# mega_pinout.net
KiCad netlist of a schematic drawn in EAGLE
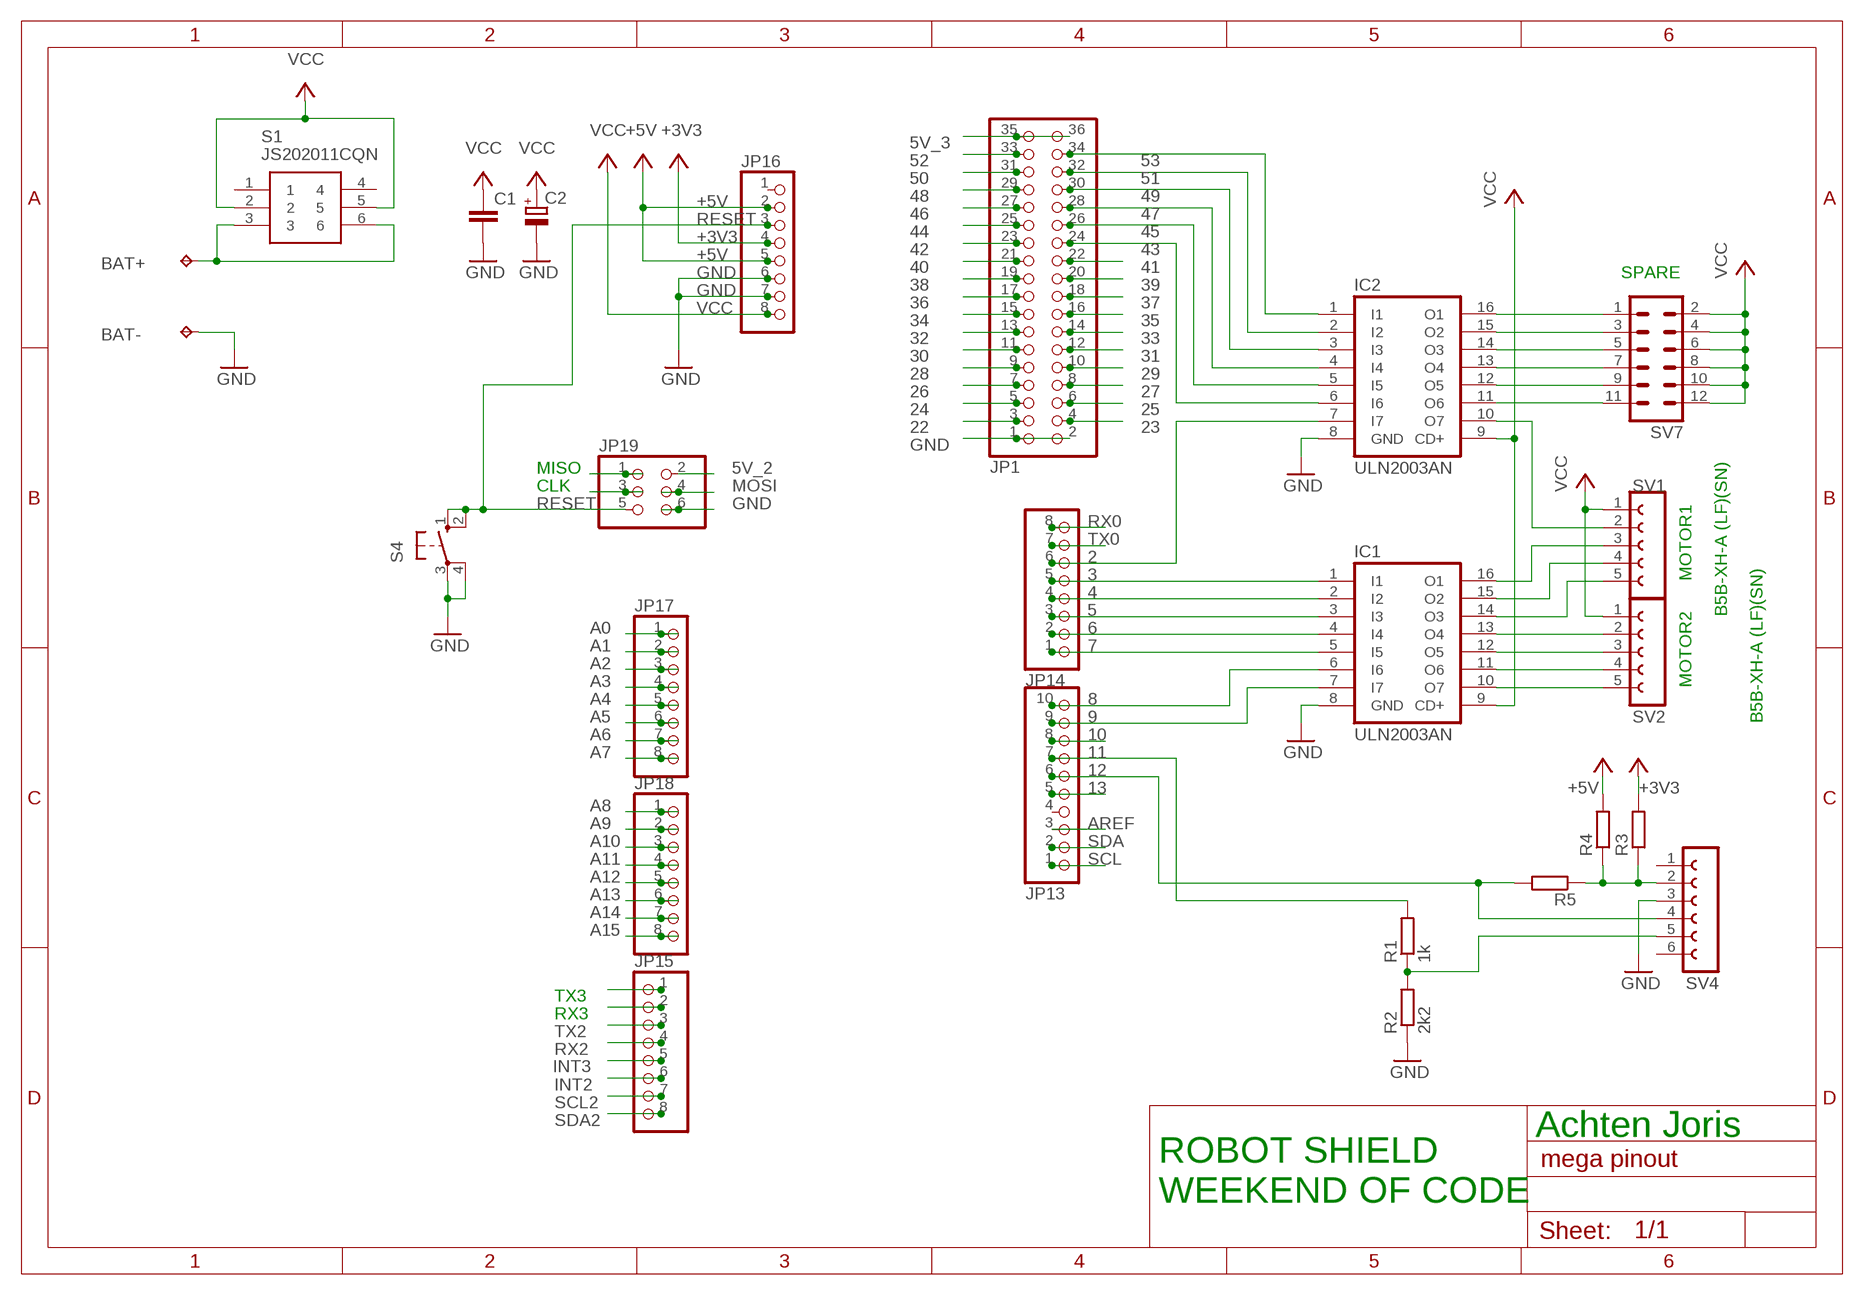
[diagram p0: schematic, sheet 1]

(export (version "E")
  (design (tool "Eeschema 10.0.6"))
  (components
    (comp (ref "BAT+")
      (value "TPPAD1-13")
      (footprint "eagle-import:P1-13")
      (libsource (lib "eagle-import") (part "TPPAD1-13"))
    )
    (comp (ref "BAT-")
      (value "TPPAD1-13")
      (footprint "eagle-import:P1-13")
      (libsource (lib "eagle-import") (part "TPPAD1-13"))
    )
    (comp (ref "C1")
      (value "C-EUC1206")
      (footprint "eagle-import:C1206")
      (libsource (lib "eagle-import") (part "C-EUC1206"))
    )
    (comp (ref "C2")
      (value "CPOL-EUE5-8.5")
      (footprint "eagle-import:E5-8,5")
      (libsource (lib "eagle-import") (part "CPOL-EUE5-8.5"))
    )
    (comp (ref "IC1")
      (value "ULN2003AN")
      (footprint "eagle-import:DIL16")
      (libsource (lib "eagle-import") (part "ULN2003AN"))
    )
    (comp (ref "IC2")
      (value "ULN2003AN")
      (footprint "eagle-import:DIL16")
      (libsource (lib "eagle-import") (part "ULN2003AN"))
    )
    (comp (ref "JP1")
      (value "PINHD-2X18")
      (footprint "eagle-import:2X18")
      (libsource (lib "eagle-import") (part "PINHD-2X18"))
    )
    (comp (ref "JP13")
      (value "PINHD-1X10")
      (footprint "eagle-import:1X10")
      (libsource (lib "eagle-import") (part "PINHD-1X10"))
    )
    (comp (ref "JP14")
      (value "PINHD-1X8")
      (footprint "eagle-import:1X08")
      (libsource (lib "eagle-import") (part "PINHD-1X8"))
    )
    (comp (ref "JP15")
      (value "PINHD-1X8")
      (footprint "eagle-import:1X08")
      (libsource (lib "eagle-import") (part "PINHD-1X8"))
    )
    (comp (ref "JP16")
      (value "PINHD-1X8")
      (footprint "eagle-import:1X08")
      (libsource (lib "eagle-import") (part "PINHD-1X8"))
    )
    (comp (ref "JP17")
      (value "PINHD-1X8")
      (footprint "eagle-import:1X08")
      (libsource (lib "eagle-import") (part "PINHD-1X8"))
    )
    (comp (ref "JP18")
      (value "PINHD-1X8")
      (footprint "eagle-import:1X08")
      (libsource (lib "eagle-import") (part "PINHD-1X8"))
    )
    (comp (ref "JP19")
      (value "PINHD-2X3")
      (footprint "eagle-import:2X03")
      (libsource (lib "eagle-import") (part "PINHD-2X3"))
    )
    (comp (ref "R1")
      (value "1k")
      (footprint "eagle-import:R0603")
      (libsource (lib "eagle-import") (part "R-EU_R0603"))
    )
    (comp (ref "R2")
      (value "2k2")
      (footprint "eagle-import:R0603")
      (libsource (lib "eagle-import") (part "R-EU_R0603"))
    )
    (comp (ref "R3")
      (value "R-EU_R0603")
      (footprint "eagle-import:R0603")
      (libsource (lib "eagle-import") (part "R-EU_R0603"))
    )
    (comp (ref "R4")
      (value "R-EU_R0603")
      (footprint "eagle-import:R0603")
      (libsource (lib "eagle-import") (part "R-EU_R0603"))
    )
    (comp (ref "R5")
      (value "R-EU_R0603")
      (footprint "eagle-import:R0603")
      (libsource (lib "eagle-import") (part "R-EU_R0603"))
    )
    (comp (ref "S1")
      (value "JS202011CQN")
      (footprint "eagle-import:JS202011CQN")
      (fields (field (name "MOUSER_PART_NUMBER") "611-JS202011CQN"))
      (libsource (lib "eagle-import") (part "JS202011CQN"))
    )
    (comp (ref "S4")
      (value "10-XX")
      (footprint "eagle-import:B3F-10XX")
      (fields (field (name "MPN") "B3F-1000"))
      (libsource (lib "eagle-import") (part "10-XX"))
    )
    (comp (ref "SV1")
      (value "FE05-1")
      (footprint "eagle-import:FE05-1")
      (libsource (lib "eagle-import") (part "FE05-1"))
    )
    (comp (ref "SV2")
      (value "FE05-1")
      (footprint "eagle-import:FE05-1")
      (libsource (lib "eagle-import") (part "FE05-1"))
    )
    (comp (ref "SV4")
      (value "FE06-1")
      (footprint "eagle-import:FE06")
      (libsource (lib "eagle-import") (part "FE06-1"))
    )
    (comp (ref "SV7")
      (value "MA06-2")
      (footprint "eagle-import:MA06-2")
      (libsource (lib "eagle-import") (part "MA06-2"))
    )
  )
  (nets
    (net (code "1") (name "+3V3") (class "Default")
      (node (ref "JP16") (pin "4") (pinfunction "4_4") (pintype "passive"))
      (node (ref "R3") (pin "2") (pinfunction "2_2") (pintype "passive"))
    )
    (net (code "2") (name "+5V") (class "Default")
      (node (ref "JP16") (pin "2") (pinfunction "2_2") (pintype "passive"))
      (node (ref "JP16") (pin "5") (pinfunction "5_5") (pintype "passive"))
      (node (ref "R4") (pin "2") (pinfunction "2_2") (pintype "passive"))
    )
    (net (code "3") (name "/2") (class "Default")
      (node (ref "IC2") (pin "7") (pinfunction "I7_7") (pintype "input"))
      (node (ref "JP14") (pin "6") (pinfunction "6_6") (pintype "passive"))
    )
    (net (code "4") (name "/3") (class "Default")
      (node (ref "IC1") (pin "1") (pinfunction "I1_1") (pintype "input"))
      (node (ref "JP14") (pin "5") (pinfunction "5_5") (pintype "passive"))
    )
    (net (code "5") (name "/4") (class "Default")
      (node (ref "IC1") (pin "2") (pinfunction "I2_2") (pintype "input"))
      (node (ref "JP14") (pin "4") (pinfunction "4_4") (pintype "passive"))
    )
    (net (code "6") (name "/5") (class "Default")
      (node (ref "IC1") (pin "3") (pinfunction "I3_3") (pintype "input"))
      (node (ref "JP14") (pin "3") (pinfunction "3_3") (pintype "passive"))
    )
    (net (code "7") (name "/5V_2") (class "Default")
      (node (ref "JP19") (pin "2") (pinfunction "2_2") (pintype "passive"))
    )
    (net (code "8") (name "/5V_3") (class "Default")
      (node (ref "JP1") (pin "35") (pinfunction "35_35") (pintype "passive"))
      (node (ref "JP1") (pin "36") (pinfunction "36_36") (pintype "passive"))
    )
    (net (code "9") (name "/6") (class "Default")
      (node (ref "IC1") (pin "4") (pinfunction "I4_4") (pintype "input"))
      (node (ref "JP14") (pin "2") (pinfunction "2_2") (pintype "passive"))
    )
    (net (code "10") (name "/7") (class "Default")
      (node (ref "IC1") (pin "5") (pinfunction "I5_5") (pintype "input"))
      (node (ref "JP14") (pin "1") (pinfunction "1_1") (pintype "passive"))
    )
    (net (code "11") (name "/8") (class "Default")
      (node (ref "IC1") (pin "6") (pinfunction "I6_6") (pintype "input"))
      (node (ref "JP13") (pin "10") (pinfunction "10_10") (pintype "passive"))
    )
    (net (code "12") (name "/9") (class "Default")
      (node (ref "IC1") (pin "7") (pinfunction "I7_7") (pintype "input"))
      (node (ref "JP13") (pin "9") (pinfunction "9_9") (pintype "passive"))
    )
    (net (code "13") (name "/10") (class "Default")
      (node (ref "JP13") (pin "8") (pinfunction "8_8") (pintype "passive"))
    )
    (net (code "14") (name "/11") (class "Default")
      (node (ref "JP13") (pin "7") (pinfunction "7_7") (pintype "passive"))
      (node (ref "R1") (pin "2") (pinfunction "2_2") (pintype "passive"))
    )
    (net (code "15") (name "/12") (class "Default")
      (node (ref "JP13") (pin "6") (pinfunction "6_6") (pintype "passive"))
      (node (ref "R5") (pin "2") (pinfunction "2_2") (pintype "passive"))
      (node (ref "SV4") (pin "4") (pinfunction "4_4") (pintype "passive"))
    )
    (net (code "16") (name "/13") (class "Default")
      (node (ref "JP13") (pin "5") (pinfunction "5_5") (pintype "passive"))
    )
    (net (code "17") (name "/22") (class "Default")
      (node (ref "JP1") (pin "3") (pinfunction "3_3") (pintype "passive"))
    )
    (net (code "18") (name "/23") (class "Default")
      (node (ref "JP1") (pin "4") (pinfunction "4_4") (pintype "passive"))
    )
    (net (code "19") (name "/24") (class "Default")
      (node (ref "JP1") (pin "5") (pinfunction "5_5") (pintype "passive"))
    )
    (net (code "20") (name "/25") (class "Default")
      (node (ref "JP1") (pin "6") (pinfunction "6_6") (pintype "passive"))
    )
    (net (code "21") (name "/26") (class "Default")
      (node (ref "JP1") (pin "7") (pinfunction "7_7") (pintype "passive"))
    )
    (net (code "22") (name "/27") (class "Default")
      (node (ref "JP1") (pin "8") (pinfunction "8_8") (pintype "passive"))
    )
    (net (code "23") (name "/28") (class "Default")
      (node (ref "JP1") (pin "9") (pinfunction "9_9") (pintype "passive"))
    )
    (net (code "24") (name "/29") (class "Default")
      (node (ref "JP1") (pin "10") (pinfunction "10_10") (pintype "passive"))
    )
    (net (code "25") (name "/30") (class "Default")
      (node (ref "JP1") (pin "11") (pinfunction "11_11") (pintype "passive"))
    )
    (net (code "26") (name "/31") (class "Default")
      (node (ref "JP1") (pin "12") (pinfunction "12_12") (pintype "passive"))
    )
    (net (code "27") (name "/32") (class "Default")
      (node (ref "JP1") (pin "13") (pinfunction "13_13") (pintype "passive"))
    )
    (net (code "28") (name "/33") (class "Default")
      (node (ref "JP1") (pin "14") (pinfunction "14_14") (pintype "passive"))
    )
    (net (code "29") (name "/34") (class "Default")
      (node (ref "JP1") (pin "15") (pinfunction "15_15") (pintype "passive"))
    )
    (net (code "30") (name "/35") (class "Default")
      (node (ref "JP1") (pin "16") (pinfunction "16_16") (pintype "passive"))
    )
    (net (code "31") (name "/36") (class "Default")
      (node (ref "JP1") (pin "17") (pinfunction "17_17") (pintype "passive"))
    )
    (net (code "32") (name "/37") (class "Default")
      (node (ref "JP1") (pin "18") (pinfunction "18_18") (pintype "passive"))
    )
    (net (code "33") (name "/38") (class "Default")
      (node (ref "JP1") (pin "19") (pinfunction "19_19") (pintype "passive"))
    )
    (net (code "34") (name "/39") (class "Default")
      (node (ref "JP1") (pin "20") (pinfunction "20_20") (pintype "passive"))
    )
    (net (code "35") (name "/40") (class "Default")
      (node (ref "JP1") (pin "21") (pinfunction "21_21") (pintype "passive"))
    )
    (net (code "36") (name "/41") (class "Default")
      (node (ref "JP1") (pin "22") (pinfunction "22_22") (pintype "passive"))
    )
    (net (code "37") (name "/42") (class "Default")
      (node (ref "JP1") (pin "23") (pinfunction "23_23") (pintype "passive"))
    )
    (net (code "38") (name "/43") (class "Default")
      (node (ref "IC2") (pin "6") (pinfunction "I6_6") (pintype "input"))
      (node (ref "JP1") (pin "24") (pinfunction "24_24") (pintype "passive"))
    )
    (net (code "39") (name "/44") (class "Default")
      (node (ref "JP1") (pin "25") (pinfunction "25_25") (pintype "passive"))
    )
    (net (code "40") (name "/45") (class "Default")
      (node (ref "IC2") (pin "5") (pinfunction "I5_5") (pintype "input"))
      (node (ref "JP1") (pin "26") (pinfunction "26_26") (pintype "passive"))
    )
    (net (code "41") (name "/46") (class "Default")
      (node (ref "JP1") (pin "27") (pinfunction "27_27") (pintype "passive"))
    )
    (net (code "42") (name "/47") (class "Default")
      (node (ref "IC2") (pin "4") (pinfunction "I4_4") (pintype "input"))
      (node (ref "JP1") (pin "28") (pinfunction "28_28") (pintype "passive"))
    )
    (net (code "43") (name "/48") (class "Default")
      (node (ref "JP1") (pin "29") (pinfunction "29_29") (pintype "passive"))
    )
    (net (code "44") (name "/49") (class "Default")
      (node (ref "IC2") (pin "3") (pinfunction "I3_3") (pintype "input"))
      (node (ref "JP1") (pin "30") (pinfunction "30_30") (pintype "passive"))
    )
    (net (code "45") (name "/50") (class "Default")
      (node (ref "JP1") (pin "31") (pinfunction "31_31") (pintype "passive"))
    )
    (net (code "46") (name "/51") (class "Default")
      (node (ref "IC2") (pin "2") (pinfunction "I2_2") (pintype "input"))
      (node (ref "JP1") (pin "32") (pinfunction "32_32") (pintype "passive"))
    )
    (net (code "47") (name "/52") (class "Default")
      (node (ref "JP1") (pin "33") (pinfunction "33_33") (pintype "passive"))
    )
    (net (code "48") (name "/53") (class "Default")
      (node (ref "IC2") (pin "1") (pinfunction "I1_1") (pintype "input"))
      (node (ref "JP1") (pin "34") (pinfunction "34_34") (pintype "passive"))
    )
    (net (code "49") (name "/A0") (class "Default")
      (node (ref "JP17") (pin "1") (pinfunction "1_1") (pintype "passive"))
    )
    (net (code "50") (name "/A1") (class "Default")
      (node (ref "JP17") (pin "2") (pinfunction "2_2") (pintype "passive"))
    )
    (net (code "51") (name "/A2") (class "Default")
      (node (ref "JP17") (pin "3") (pinfunction "3_3") (pintype "passive"))
    )
    (net (code "52") (name "/A3") (class "Default")
      (node (ref "JP17") (pin "4") (pinfunction "4_4") (pintype "passive"))
    )
    (net (code "53") (name "/A4") (class "Default")
      (node (ref "JP17") (pin "5") (pinfunction "5_5") (pintype "passive"))
    )
    (net (code "54") (name "/A5") (class "Default")
      (node (ref "JP17") (pin "6") (pinfunction "6_6") (pintype "passive"))
    )
    (net (code "55") (name "/A6") (class "Default")
      (node (ref "JP17") (pin "7") (pinfunction "7_7") (pintype "passive"))
    )
    (net (code "56") (name "/A7") (class "Default")
      (node (ref "JP17") (pin "8") (pinfunction "8_8") (pintype "passive"))
    )
    (net (code "57") (name "/A8") (class "Default")
      (node (ref "JP18") (pin "1") (pinfunction "1_1") (pintype "passive"))
    )
    (net (code "58") (name "/A9") (class "Default")
      (node (ref "JP18") (pin "2") (pinfunction "2_2") (pintype "passive"))
    )
    (net (code "59") (name "/A10") (class "Default")
      (node (ref "JP18") (pin "3") (pinfunction "3_3") (pintype "passive"))
    )
    (net (code "60") (name "/A11") (class "Default")
      (node (ref "JP18") (pin "4") (pinfunction "4_4") (pintype "passive"))
    )
    (net (code "61") (name "/A12") (class "Default")
      (node (ref "JP18") (pin "5") (pinfunction "5_5") (pintype "passive"))
    )
    (net (code "62") (name "/A13") (class "Default")
      (node (ref "JP18") (pin "6") (pinfunction "6_6") (pintype "passive"))
    )
    (net (code "63") (name "/A14") (class "Default")
      (node (ref "JP18") (pin "7") (pinfunction "7_7") (pintype "passive"))
    )
    (net (code "64") (name "/A15") (class "Default")
      (node (ref "JP18") (pin "8") (pinfunction "8_8") (pintype "passive"))
    )
    (net (code "65") (name "/AREF") (class "Default")
      (node (ref "JP13") (pin "3") (pinfunction "3_3") (pintype "passive"))
    )
    (net (code "66") (name "/CLK") (class "Default")
      (node (ref "JP19") (pin "3") (pinfunction "3_3") (pintype "passive"))
    )
    (net (code "67") (name "/INT2") (class "Default")
      (node (ref "JP15") (pin "6") (pinfunction "6_6") (pintype "passive"))
    )
    (net (code "68") (name "/INT3") (class "Default")
      (node (ref "JP15") (pin "5") (pinfunction "5_5") (pintype "passive"))
    )
    (net (code "69") (name "/MISO") (class "Default")
      (node (ref "JP19") (pin "1") (pinfunction "1_1") (pintype "passive"))
    )
    (net (code "70") (name "/MOSI") (class "Default")
      (node (ref "JP19") (pin "4") (pinfunction "4_4") (pintype "passive"))
    )
    (net (code "71") (name "/RESET") (class "Default")
      (node (ref "JP16") (pin "3") (pinfunction "3_3") (pintype "passive"))
      (node (ref "JP19") (pin "5") (pinfunction "5_5") (pintype "passive"))
      (node (ref "S4") (pin "1") (pinfunction "S_1") (pintype "passive"))
      (node (ref "S4") (pin "2") (pinfunction "S1_2") (pintype "passive"))
    )
    (net (code "72") (name "/RX0") (class "Default")
      (node (ref "JP14") (pin "8") (pinfunction "8_8") (pintype "passive"))
    )
    (net (code "73") (name "/RX2") (class "Default")
      (node (ref "JP15") (pin "4") (pinfunction "4_4") (pintype "passive"))
    )
    (net (code "74") (name "/RX3") (class "Default")
      (node (ref "JP15") (pin "2") (pinfunction "2_2") (pintype "passive"))
    )
    (net (code "75") (name "/SCL") (class "Default")
      (node (ref "JP13") (pin "1") (pinfunction "1_1") (pintype "passive"))
    )
    (net (code "76") (name "/SCL2") (class "Default")
      (node (ref "JP15") (pin "7") (pinfunction "7_7") (pintype "passive"))
    )
    (net (code "77") (name "/SDA") (class "Default")
      (node (ref "JP13") (pin "2") (pinfunction "2_2") (pintype "passive"))
    )
    (net (code "78") (name "/SDA2") (class "Default")
      (node (ref "JP15") (pin "8") (pinfunction "8_8") (pintype "passive"))
    )
    (net (code "79") (name "/TX0") (class "Default")
      (node (ref "JP14") (pin "7") (pinfunction "7_7") (pintype "passive"))
    )
    (net (code "80") (name "/TX2") (class "Default")
      (node (ref "JP15") (pin "3") (pinfunction "3_3") (pintype "passive"))
    )
    (net (code "81") (name "/TX3") (class "Default")
      (node (ref "JP15") (pin "1") (pinfunction "1_1") (pintype "passive"))
    )
    (net (code "82") (name "GND") (class "Default")
      (node (ref "BAT-") (pin "TP") (pinfunction "TP_TP") (pintype "input"))
      (node (ref "C1") (pin "2") (pinfunction "2_2") (pintype "passive"))
      (node (ref "C2") (pin "-") (pinfunction "-_-") (pintype "passive"))
      (node (ref "IC1") (pin "8") (pinfunction "GND_8") (pintype "power_in"))
      (node (ref "IC2") (pin "8") (pinfunction "GND_8") (pintype "power_in"))
      (node (ref "JP1") (pin "1") (pinfunction "1_1") (pintype "passive"))
      (node (ref "JP1") (pin "2") (pinfunction "2_2") (pintype "passive"))
      (node (ref "JP16") (pin "6") (pinfunction "6_6") (pintype "passive"))
      (node (ref "JP16") (pin "7") (pinfunction "7_7") (pintype "passive"))
      (node (ref "JP19") (pin "6") (pinfunction "6_6") (pintype "passive"))
      (node (ref "R2") (pin "1") (pinfunction "1_1") (pintype "passive"))
      (node (ref "S4") (pin "3") (pinfunction "P_3") (pintype "passive"))
      (node (ref "S4") (pin "4") (pinfunction "P1_4") (pintype "passive"))
      (node (ref "SV4") (pin "3") (pinfunction "3_3") (pintype "passive"))
    )
    (net (code "83") (name "Net-(BAT+-PadTP)") (class "Default")
      (node (ref "BAT+") (pin "TP") (pinfunction "TP_TP") (pintype "input"))
      (node (ref "S1") (pin "3") (pinfunction "3_3") (pintype "bidirectional"))
      (node (ref "S1") (pin "6") (pinfunction "6_6") (pintype "bidirectional"))
    )
    (net (code "84") (name "Net-(IC1-O1)") (class "Default")
      (node (ref "IC1") (pin "16") (pinfunction "O1_16") (pintype "open_collector"))
      (node (ref "SV1") (pin "3") (pinfunction "3_3") (pintype "passive"))
    )
    (net (code "85") (name "Net-(IC1-O2)") (class "Default")
      (node (ref "IC1") (pin "15") (pinfunction "O2_15") (pintype "open_collector"))
      (node (ref "SV1") (pin "4") (pinfunction "4_4") (pintype "passive"))
    )
    (net (code "86") (name "Net-(IC1-O3)") (class "Default")
      (node (ref "IC1") (pin "14") (pinfunction "O3_14") (pintype "open_collector"))
      (node (ref "SV1") (pin "5") (pinfunction "5_5") (pintype "passive"))
    )
    (net (code "87") (name "Net-(IC1-O4)") (class "Default")
      (node (ref "IC1") (pin "13") (pinfunction "O4_13") (pintype "open_collector"))
      (node (ref "SV2") (pin "2") (pinfunction "2_2") (pintype "passive"))
    )
    (net (code "88") (name "Net-(IC1-O5)") (class "Default")
      (node (ref "IC1") (pin "12") (pinfunction "O5_12") (pintype "open_collector"))
      (node (ref "SV2") (pin "3") (pinfunction "3_3") (pintype "passive"))
    )
    (net (code "89") (name "Net-(IC1-O6)") (class "Default")
      (node (ref "IC1") (pin "11") (pinfunction "O6_11") (pintype "open_collector"))
      (node (ref "SV2") (pin "4") (pinfunction "4_4") (pintype "passive"))
    )
    (net (code "90") (name "Net-(IC1-O7)") (class "Default")
      (node (ref "IC1") (pin "10") (pinfunction "O7_10") (pintype "open_collector"))
      (node (ref "SV2") (pin "5") (pinfunction "5_5") (pintype "passive"))
    )
    (net (code "91") (name "Net-(IC2-O1)") (class "Default")
      (node (ref "IC2") (pin "16") (pinfunction "O1_16") (pintype "open_collector"))
      (node (ref "SV7") (pin "1") (pinfunction "1_1") (pintype "passive"))
    )
    (net (code "92") (name "Net-(IC2-O2)") (class "Default")
      (node (ref "IC2") (pin "15") (pinfunction "O2_15") (pintype "open_collector"))
      (node (ref "SV7") (pin "3") (pinfunction "3_3") (pintype "passive"))
    )
    (net (code "93") (name "Net-(IC2-O3)") (class "Default")
      (node (ref "IC2") (pin "14") (pinfunction "O3_14") (pintype "open_collector"))
      (node (ref "SV7") (pin "5") (pinfunction "5_5") (pintype "passive"))
    )
    (net (code "94") (name "Net-(IC2-O4)") (class "Default")
      (node (ref "IC2") (pin "13") (pinfunction "O4_13") (pintype "open_collector"))
      (node (ref "SV7") (pin "7") (pinfunction "7_7") (pintype "passive"))
    )
    (net (code "95") (name "Net-(IC2-O5)") (class "Default")
      (node (ref "IC2") (pin "12") (pinfunction "O5_12") (pintype "open_collector"))
      (node (ref "SV7") (pin "9") (pinfunction "9_9") (pintype "passive"))
    )
    (net (code "96") (name "Net-(IC2-O6)") (class "Default")
      (node (ref "IC2") (pin "11") (pinfunction "O6_11") (pintype "open_collector"))
      (node (ref "SV7") (pin "11") (pinfunction "11_11") (pintype "passive"))
    )
    (net (code "97") (name "Net-(IC2-O7)") (class "Default")
      (node (ref "IC2") (pin "10") (pinfunction "O7_10") (pintype "open_collector"))
      (node (ref "SV1") (pin "2") (pinfunction "2_2") (pintype "passive"))
    )
    (net (code "98") (name "Net-(R1-Pad1)") (class "Default")
      (node (ref "R1") (pin "1") (pinfunction "1_1") (pintype "passive"))
      (node (ref "R2") (pin "2") (pinfunction "2_2") (pintype "passive"))
      (node (ref "SV4") (pin "5") (pinfunction "5_5") (pintype "passive"))
    )
    (net (code "99") (name "Net-(R3-Pad1)") (class "Default")
      (node (ref "R3") (pin "1") (pinfunction "1_1") (pintype "passive"))
      (node (ref "R4") (pin "1") (pinfunction "1_1") (pintype "passive"))
      (node (ref "R5") (pin "1") (pinfunction "1_1") (pintype "passive"))
      (node (ref "SV4") (pin "2") (pinfunction "2_2") (pintype "passive"))
    )
    (net (code "100") (name "VCC") (class "Default")
      (node (ref "C1") (pin "1") (pinfunction "1_1") (pintype "passive"))
      (node (ref "C2") (pin "+") (pinfunction "+_+") (pintype "passive"))
      (node (ref "IC1") (pin "9") (pinfunction "CD+_9") (pintype "passive"))
      (node (ref "IC2") (pin "9") (pinfunction "CD+_9") (pintype "passive"))
      (node (ref "JP16") (pin "8") (pinfunction "8_8") (pintype "passive"))
      (node (ref "S1") (pin "2") (pinfunction "2_2") (pintype "bidirectional"))
      (node (ref "S1") (pin "5") (pinfunction "5_5") (pintype "bidirectional"))
      (node (ref "SV1") (pin "1") (pinfunction "1_1") (pintype "passive"))
      (node (ref "SV2") (pin "1") (pinfunction "1_1") (pintype "passive"))
      (node (ref "SV7") (pin "10") (pinfunction "10_10") (pintype "passive"))
      (node (ref "SV7") (pin "12") (pinfunction "12_12") (pintype "passive"))
      (node (ref "SV7") (pin "2") (pinfunction "2_2") (pintype "passive"))
      (node (ref "SV7") (pin "4") (pinfunction "4_4") (pintype "passive"))
      (node (ref "SV7") (pin "6") (pinfunction "6_6") (pintype "passive"))
      (node (ref "SV7") (pin "8") (pinfunction "8_8") (pintype "passive"))
    )
    (net (code "101") (name "unconnected-(JP13-Pad4)") (class "Default")
      (node (ref "JP13") (pin "4") (pinfunction "4_4") (pintype "passive"))
    )
    (net (code "102") (name "unconnected-(JP16-Pad1)") (class "Default")
      (node (ref "JP16") (pin "1") (pinfunction "1_1") (pintype "passive"))
    )
    (net (code "103") (name "unconnected-(S1-Pad1)") (class "Default")
      (node (ref "S1") (pin "1") (pinfunction "1_1") (pintype "bidirectional"))
    )
    (net (code "104") (name "unconnected-(S1-Pad4)") (class "Default")
      (node (ref "S1") (pin "4") (pinfunction "4_4") (pintype "bidirectional"))
    )
    (net (code "105") (name "unconnected-(SV4-Pad1)") (class "Default")
      (node (ref "SV4") (pin "1") (pinfunction "1_1") (pintype "passive"))
    )
    (net (code "106") (name "unconnected-(SV4-Pad6)") (class "Default")
      (node (ref "SV4") (pin "6") (pinfunction "6_6") (pintype "passive"))
    )
  )
)
